# Interfaces_and_Connectors.net
KiCad netlist of a schematic drawn in Altium Designer
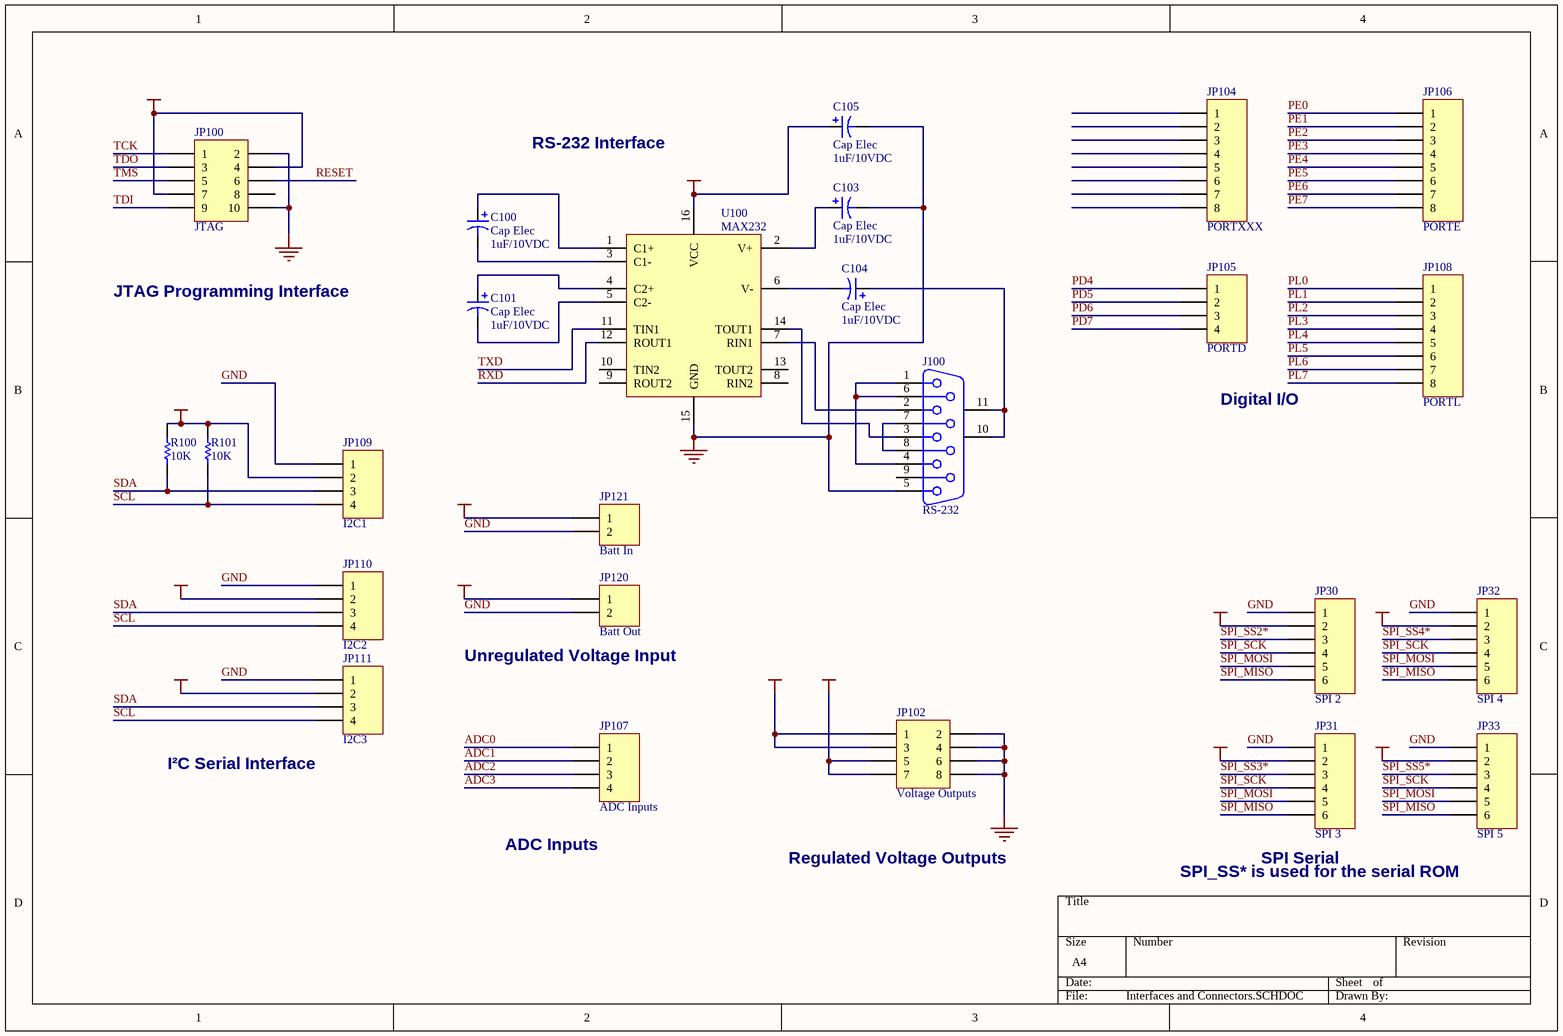
[diagram p0: Interfaces and Connectors.SCHDOC]

(export (version "E")
  (design (tool "Eeschema 10.0.6"))
  (components
    (comp (ref "C100")
      (value "Cap Elec")
      (footprint "CAPR5-4X5")
      (description "Polarized Capacitor (Axial)")
      (fields (field (name "ALTIUM_VALUE") "1uF/10VDC") (field (name "PUBLISHER") "Altium Limited"))
      (libsource (lib "Miscellaneous Devices") (part "Cap Pol2"))
    )
    (comp (ref "C101")
      (value "Cap Elec")
      (footprint "CAPR5-4X5")
      (description "Polarized Capacitor (Axial)")
      (fields (field (name "ALTIUM_VALUE") "1uF/10VDC") (field (name "PUBLISHER") "Altium Limited"))
      (libsource (lib "Miscellaneous Devices") (part "Cap Pol2"))
    )
    (comp (ref "C103")
      (value "Cap Elec")
      (footprint "CAPR5-4X5")
      (description "Polarized Capacitor (Axial)")
      (fields (field (name "ALTIUM_VALUE") "1uF/10VDC") (field (name "PUBLISHER") "Altium Limited"))
      (libsource (lib "Miscellaneous Devices") (part "Cap Pol2"))
    )
    (comp (ref "C104")
      (value "Cap Elec")
      (footprint "CAPR5-4X5")
      (description "Polarized Capacitor (Axial)")
      (fields (field (name "ALTIUM_VALUE") "1uF/10VDC") (field (name "PUBLISHER") "Altium Limited"))
      (libsource (lib "Miscellaneous Devices") (part "Cap Pol2"))
    )
    (comp (ref "C105")
      (value "Cap Elec")
      (footprint "CAPR5-4X5")
      (description "Polarized Capacitor (Axial)")
      (fields (field (name "ALTIUM_VALUE") "1uF/10VDC") (field (name "PUBLISHER") "Altium Limited"))
      (libsource (lib "Miscellaneous Devices") (part "Cap Pol2"))
    )
    (comp (ref "J100")
      (value "RS-232")
      (footprint "DSUB1.385-2H9")
      (description "Receptacle Assembly, 9 Position, Right Angle")
      (fields (field (name "PUBLISHER") "Altium Limited"))
      (libsource (lib "Miscellaneous Connectors") (part "D Connector 9"))
    )
    (comp (ref "JP30")
      (value "SPI 2")
      (footprint "HDR1X6")
      (description "Header, 6-Pin")
      (fields (field (name "PUBLISHER") "Altium Limited"))
      (libsource (lib "Miscellaneous Connectors") (part "Header 6"))
    )
    (comp (ref "JP31")
      (value "SPI 3")
      (footprint "HDR1X6")
      (description "Header, 6-Pin")
      (fields (field (name "PUBLISHER") "Altium Limited"))
      (libsource (lib "Miscellaneous Connectors") (part "Header 6"))
    )
    (comp (ref "JP32")
      (value "SPI 4")
      (footprint "HDR1X6")
      (description "Header, 6-Pin")
      (fields (field (name "PUBLISHER") "Altium Limited"))
      (libsource (lib "Miscellaneous Connectors") (part "Header 6"))
    )
    (comp (ref "JP33")
      (value "SPI 5")
      (footprint "HDR1X6")
      (description "Header, 6-Pin")
      (fields (field (name "PUBLISHER") "Altium Limited"))
      (libsource (lib "Miscellaneous Connectors") (part "Header 6"))
    )
    (comp (ref "JP100")
      (value "JTAG")
      (footprint "HDR2X5")
      (description "Header, 5-Pin, Dual row")
      (fields (field (name "PUBLISHER") "Altium Limited"))
      (libsource (lib "Miscellaneous Connectors") (part "Header 5X2"))
    )
    (comp (ref "JP102")
      (value "Voltage Outputs")
      (footprint "HDR2X4")
      (description "Header, 4-Pin, Dual row")
      (fields (field (name "PUBLISHER") "Altium Limited"))
      (libsource (lib "Miscellaneous Connectors") (part "Header 4X2"))
    )
    (comp (ref "JP104")
      (value "PORTXXX")
      (footprint "HDR1X8")
      (description "Header, 8-Pin")
      (fields (field (name "PUBLISHER") "Altium Limited"))
      (libsource (lib "Miscellaneous Connectors") (part "Header 8"))
    )
    (comp (ref "JP105")
      (value "PORTD")
      (footprint "HDR1X4")
      (description "Header, 4-Pin")
      (fields (field (name "PUBLISHER") "Altium Limited"))
      (libsource (lib "Miscellaneous Connectors") (part "Header 4"))
    )
    (comp (ref "JP106")
      (value "PORTE")
      (footprint "HDR1X8")
      (description "Header, 8-Pin")
      (fields (field (name "PUBLISHER") "Altium Limited"))
      (libsource (lib "Miscellaneous Connectors") (part "Header 8"))
    )
    (comp (ref "JP107")
      (value "ADC Inputs")
      (footprint "HDR1X4")
      (description "Header, 4-Pin")
      (fields (field (name "PUBLISHER") "Altium Limited"))
      (libsource (lib "Miscellaneous Connectors") (part "Header 4"))
    )
    (comp (ref "JP108")
      (value "PORTL")
      (footprint "HDR1X8")
      (description "Header, 8-Pin")
      (fields (field (name "PUBLISHER") "Altium Limited"))
      (libsource (lib "Miscellaneous Connectors") (part "Header 8"))
    )
    (comp (ref "JP109")
      (value "I2C1")
      (footprint "HDR1X4")
      (description "Header, 4-Pin")
      (fields (field (name "PUBLISHER") "Altium Limited"))
      (libsource (lib "Miscellaneous Connectors") (part "Header 4"))
    )
    (comp (ref "JP110")
      (value "I2C2")
      (footprint "HDR1X4")
      (description "Header, 4-Pin")
      (fields (field (name "PUBLISHER") "Altium Limited"))
      (libsource (lib "Miscellaneous Connectors") (part "Header 4"))
    )
    (comp (ref "JP111")
      (value "I2C3")
      (footprint "HDR1X4")
      (description "Header, 4-Pin")
      (fields (field (name "PUBLISHER") "Altium Limited"))
      (libsource (lib "Miscellaneous Connectors") (part "Header 4"))
    )
    (comp (ref "JP120")
      (value "Batt Out")
      (footprint "HDR1X2")
      (description "Header, 2-Pin")
      (fields (field (name "PUBLISHER") "Altium Limited"))
      (libsource (lib "Miscellaneous Connectors") (part "Header 2"))
    )
    (comp (ref "JP121")
      (value "Batt In")
      (footprint "HDR1X2")
      (description "Header, 2-Pin")
      (fields (field (name "PUBLISHER") "Altium Limited"))
      (libsource (lib "Miscellaneous Connectors") (part "Header 2"))
    )
    (comp (ref "R100")
      (value "10K")
      (footprint "AXIAL-0.3")
      (description "Resistor")
      (fields (field (name "PUBLISHER") "Altium Limited"))
      (libsource (lib "Miscellaneous Devices") (part "Res1"))
    )
    (comp (ref "R101")
      (value "10K")
      (footprint "AXIAL-0.3")
      (description "Resistor")
      (fields (field (name "PUBLISHER") "Altium Limited"))
      (libsource (lib "Miscellaneous Devices") (part "Res1"))
    )
    (comp (ref "U100")
      (value "MAX232")
      (footprint "SO-G16/C5.85")
      (description "Maxim RS-232 Transceiver")
      (libsource (lib "Schematic Library") (part "MAX232"))
    )
  )
  (nets
    (net (code "1") (name "/ADC0") (class "Default")
      (node (ref "JP107") (pin "1") (pinfunction "1_1") (pintype "passive"))
    )
    (net (code "2") (name "/ADC1") (class "Default")
      (node (ref "JP107") (pin "2") (pinfunction "2_2") (pintype "passive"))
    )
    (net (code "3") (name "/ADC2") (class "Default")
      (node (ref "JP107") (pin "3") (pinfunction "3_3") (pintype "passive"))
    )
    (net (code "4") (name "/ADC3") (class "Default")
      (node (ref "JP107") (pin "4") (pinfunction "4_4") (pintype "passive"))
    )
    (net (code "5") (name "/PD4") (class "Default")
      (node (ref "JP105") (pin "1") (pinfunction "1_1") (pintype "passive"))
    )
    (net (code "6") (name "/PD5") (class "Default")
      (node (ref "JP105") (pin "2") (pinfunction "2_2") (pintype "passive"))
    )
    (net (code "7") (name "/PD6") (class "Default")
      (node (ref "JP105") (pin "3") (pinfunction "3_3") (pintype "passive"))
    )
    (net (code "8") (name "/PD7") (class "Default")
      (node (ref "JP105") (pin "4") (pinfunction "4_4") (pintype "passive"))
    )
    (net (code "9") (name "/PE0") (class "Default")
      (node (ref "JP106") (pin "1") (pinfunction "1_1") (pintype "passive"))
    )
    (net (code "10") (name "/PE1") (class "Default")
      (node (ref "JP106") (pin "2") (pinfunction "2_2") (pintype "passive"))
    )
    (net (code "11") (name "/PE2") (class "Default")
      (node (ref "JP106") (pin "3") (pinfunction "3_3") (pintype "passive"))
    )
    (net (code "12") (name "/PE3") (class "Default")
      (node (ref "JP106") (pin "4") (pinfunction "4_4") (pintype "passive"))
    )
    (net (code "13") (name "/PE4") (class "Default")
      (node (ref "JP106") (pin "5") (pinfunction "5_5") (pintype "passive"))
    )
    (net (code "14") (name "/PE5") (class "Default")
      (node (ref "JP106") (pin "6") (pinfunction "6_6") (pintype "passive"))
    )
    (net (code "15") (name "/PE6") (class "Default")
      (node (ref "JP106") (pin "7") (pinfunction "7_7") (pintype "passive"))
    )
    (net (code "16") (name "/PE7") (class "Default")
      (node (ref "JP106") (pin "8") (pinfunction "8_8") (pintype "passive"))
    )
    (net (code "17") (name "/PL0") (class "Default")
      (node (ref "JP108") (pin "1") (pinfunction "1_1") (pintype "passive"))
    )
    (net (code "18") (name "/PL1") (class "Default")
      (node (ref "JP108") (pin "2") (pinfunction "2_2") (pintype "passive"))
    )
    (net (code "19") (name "/PL2") (class "Default")
      (node (ref "JP108") (pin "3") (pinfunction "3_3") (pintype "passive"))
    )
    (net (code "20") (name "/PL3") (class "Default")
      (node (ref "JP108") (pin "4") (pinfunction "4_4") (pintype "passive"))
    )
    (net (code "21") (name "/PL4") (class "Default")
      (node (ref "JP108") (pin "5") (pinfunction "5_5") (pintype "passive"))
    )
    (net (code "22") (name "/PL5") (class "Default")
      (node (ref "JP108") (pin "6") (pinfunction "6_6") (pintype "passive"))
    )
    (net (code "23") (name "/PL6") (class "Default")
      (node (ref "JP108") (pin "7") (pinfunction "7_7") (pintype "passive"))
    )
    (net (code "24") (name "/PL7") (class "Default")
      (node (ref "JP108") (pin "8") (pinfunction "8_8") (pintype "passive"))
    )
    (net (code "25") (name "/RESET") (class "Default")
      (node (ref "JP100") (pin "6") (pinfunction "6_6") (pintype "passive"))
    )
    (net (code "26") (name "/RXD") (class "Default")
      (node (ref "U100") (pin "12") (pinfunction "ROUT1_12") (pintype "passive"))
    )
    (net (code "27") (name "/SCL") (class "Default")
      (node (ref "JP109") (pin "4") (pinfunction "4_4") (pintype "passive"))
      (node (ref "JP110") (pin "4") (pinfunction "4_4") (pintype "passive"))
      (node (ref "JP111") (pin "4") (pinfunction "4_4") (pintype "passive"))
      (node (ref "R101") (pin "1") (pinfunction "1_1") (pintype "passive"))
    )
    (net (code "28") (name "/SDA") (class "Default")
      (node (ref "JP109") (pin "3") (pinfunction "3_3") (pintype "passive"))
      (node (ref "JP110") (pin "3") (pinfunction "3_3") (pintype "passive"))
      (node (ref "JP111") (pin "3") (pinfunction "3_3") (pintype "passive"))
      (node (ref "R100") (pin "1") (pinfunction "1_1") (pintype "passive"))
    )
    (net (code "29") (name "/SPI_MISO") (class "Default")
      (node (ref "JP30") (pin "6") (pinfunction "6_6") (pintype "passive"))
      (node (ref "JP31") (pin "6") (pinfunction "6_6") (pintype "passive"))
      (node (ref "JP32") (pin "6") (pinfunction "6_6") (pintype "passive"))
      (node (ref "JP33") (pin "6") (pinfunction "6_6") (pintype "passive"))
    )
    (net (code "30") (name "/SPI_MOSI") (class "Default")
      (node (ref "JP30") (pin "5") (pinfunction "5_5") (pintype "passive"))
      (node (ref "JP31") (pin "5") (pinfunction "5_5") (pintype "passive"))
      (node (ref "JP32") (pin "5") (pinfunction "5_5") (pintype "passive"))
      (node (ref "JP33") (pin "5") (pinfunction "5_5") (pintype "passive"))
    )
    (net (code "31") (name "/SPI_SCK") (class "Default")
      (node (ref "JP30") (pin "4") (pinfunction "4_4") (pintype "passive"))
      (node (ref "JP31") (pin "4") (pinfunction "4_4") (pintype "passive"))
      (node (ref "JP32") (pin "4") (pinfunction "4_4") (pintype "passive"))
      (node (ref "JP33") (pin "4") (pinfunction "4_4") (pintype "passive"))
    )
    (net (code "32") (name "/SPI_SS2*") (class "Default")
      (node (ref "JP30") (pin "3") (pinfunction "3_3") (pintype "passive"))
    )
    (net (code "33") (name "/SPI_SS3*") (class "Default")
      (node (ref "JP31") (pin "3") (pinfunction "3_3") (pintype "passive"))
    )
    (net (code "34") (name "/SPI_SS4*") (class "Default")
      (node (ref "JP32") (pin "3") (pinfunction "3_3") (pintype "passive"))
    )
    (net (code "35") (name "/SPI_SS5*") (class "Default")
      (node (ref "JP33") (pin "3") (pinfunction "3_3") (pintype "passive"))
    )
    (net (code "36") (name "/TCK") (class "Default")
      (node (ref "JP100") (pin "1") (pinfunction "1_1") (pintype "passive"))
    )
    (net (code "37") (name "/TDI") (class "Default")
      (node (ref "JP100") (pin "9") (pinfunction "9_9") (pintype "passive"))
    )
    (net (code "38") (name "/TDO") (class "Default")
      (node (ref "JP100") (pin "3") (pinfunction "3_3") (pintype "passive"))
    )
    (net (code "39") (name "/TMS") (class "Default")
      (node (ref "JP100") (pin "5") (pinfunction "5_5") (pintype "passive"))
    )
    (net (code "40") (name "/TXD") (class "Default")
      (node (ref "U100") (pin "11") (pinfunction "TIN1_11") (pintype "passive"))
    )
    (net (code "41") (name "5V") (class "Default")
      (node (ref "C105") (pin "1") (pinfunction "1_1") (pintype "passive"))
      (node (ref "JP100") (pin "4") (pinfunction "4_4") (pintype "passive"))
      (node (ref "JP100") (pin "7") (pinfunction "7_7") (pintype "passive"))
      (node (ref "JP102") (pin "5") (pinfunction "5_5") (pintype "passive"))
      (node (ref "JP102") (pin "7") (pinfunction "7_7") (pintype "passive"))
      (node (ref "JP109") (pin "2") (pinfunction "2_2") (pintype "passive"))
      (node (ref "JP110") (pin "2") (pinfunction "2_2") (pintype "passive"))
      (node (ref "JP111") (pin "2") (pinfunction "2_2") (pintype "passive"))
      (node (ref "JP30") (pin "2") (pinfunction "2_2") (pintype "passive"))
      (node (ref "JP31") (pin "2") (pinfunction "2_2") (pintype "passive"))
      (node (ref "JP32") (pin "2") (pinfunction "2_2") (pintype "passive"))
      (node (ref "JP33") (pin "2") (pinfunction "2_2") (pintype "passive"))
      (node (ref "R100") (pin "2") (pinfunction "2_2") (pintype "passive"))
      (node (ref "R101") (pin "2") (pinfunction "2_2") (pintype "passive"))
      (node (ref "U100") (pin "16") (pinfunction "VCC_16") (pintype "passive"))
    )
    (net (code "42") (name "9V") (class "Default")
      (node (ref "JP102") (pin "1") (pinfunction "1_1") (pintype "passive"))
      (node (ref "JP102") (pin "3") (pinfunction "3_3") (pintype "passive"))
    )
    (net (code "43") (name "GND") (class "Default")
      (node (ref "C103") (pin "2") (pinfunction "2_2") (pintype "passive"))
      (node (ref "C105") (pin "2") (pinfunction "2_2") (pintype "passive"))
      (node (ref "J100") (pin "5") (pinfunction "5_5") (pintype "passive"))
      (node (ref "JP100") (pin "10") (pinfunction "10_10") (pintype "passive"))
      (node (ref "JP100") (pin "2") (pinfunction "2_2") (pintype "passive"))
      (node (ref "JP102") (pin "2") (pinfunction "2_2") (pintype "passive"))
      (node (ref "JP102") (pin "4") (pinfunction "4_4") (pintype "passive"))
      (node (ref "JP102") (pin "6") (pinfunction "6_6") (pintype "passive"))
      (node (ref "JP102") (pin "8") (pinfunction "8_8") (pintype "passive"))
      (node (ref "JP109") (pin "1") (pinfunction "1_1") (pintype "passive"))
      (node (ref "JP110") (pin "1") (pinfunction "1_1") (pintype "passive"))
      (node (ref "JP111") (pin "1") (pinfunction "1_1") (pintype "passive"))
      (node (ref "JP120") (pin "2") (pinfunction "2_2") (pintype "passive"))
      (node (ref "JP121") (pin "2") (pinfunction "2_2") (pintype "passive"))
      (node (ref "JP30") (pin "1") (pinfunction "1_1") (pintype "passive"))
      (node (ref "JP31") (pin "1") (pinfunction "1_1") (pintype "passive"))
      (node (ref "JP32") (pin "1") (pinfunction "1_1") (pintype "passive"))
      (node (ref "JP33") (pin "1") (pinfunction "1_1") (pintype "passive"))
      (node (ref "U100") (pin "15") (pinfunction "GND_15") (pintype "passive"))
    )
    (net (code "44") (name "Net-(J100-MH1)") (class "Default")
      (node (ref "C104") (pin "1") (pinfunction "1_1") (pintype "passive"))
      (node (ref "J100") (pin "10") (pinfunction "MH1_10") (pintype "passive"))
      (node (ref "J100") (pin "11") (pinfunction "MH2_11") (pintype "passive"))
    )
    (net (code "45") (name "Net-(J100-Pad1)") (class "Default")
      (node (ref "J100") (pin "1") (pinfunction "1_1") (pintype "passive"))
      (node (ref "J100") (pin "4") (pinfunction "4_4") (pintype "passive"))
      (node (ref "J100") (pin "6") (pinfunction "6_6") (pintype "passive"))
    )
    (net (code "46") (name "Net-(J100-Pad7)") (class "Default")
      (node (ref "J100") (pin "7") (pinfunction "7_7") (pintype "passive"))
      (node (ref "J100") (pin "8") (pinfunction "8_8") (pintype "passive"))
    )
    (net (code "47") (name "Net-(U100-C1+)") (class "Default")
      (node (ref "C100") (pin "1") (pinfunction "1_1") (pintype "passive"))
      (node (ref "U100") (pin "1") (pinfunction "C1+_1") (pintype "passive"))
    )
    (net (code "48") (name "Net-(U100-C1-)") (class "Default")
      (node (ref "C100") (pin "2") (pinfunction "2_2") (pintype "passive"))
      (node (ref "U100") (pin "3") (pinfunction "C1-_3") (pintype "passive"))
    )
    (net (code "49") (name "Net-(U100-C2+)") (class "Default")
      (node (ref "C101") (pin "1") (pinfunction "1_1") (pintype "passive"))
      (node (ref "U100") (pin "4") (pinfunction "C2+_4") (pintype "passive"))
    )
    (net (code "50") (name "Net-(U100-C2-)") (class "Default")
      (node (ref "C101") (pin "2") (pinfunction "2_2") (pintype "passive"))
      (node (ref "U100") (pin "5") (pinfunction "C2-_5") (pintype "passive"))
    )
    (net (code "51") (name "Net-(U100-RIN1)") (class "Default")
      (node (ref "J100") (pin "2") (pinfunction "2_2") (pintype "passive"))
      (node (ref "U100") (pin "7") (pinfunction "RIN1_7") (pintype "passive"))
    )
    (net (code "52") (name "Net-(U100-TOUT1)") (class "Default")
      (node (ref "J100") (pin "3") (pinfunction "3_3") (pintype "passive"))
      (node (ref "U100") (pin "14") (pinfunction "TOUT1_14") (pintype "passive"))
    )
    (net (code "53") (name "Net-(U100-V+)") (class "Default")
      (node (ref "C103") (pin "1") (pinfunction "1_1") (pintype "passive"))
      (node (ref "U100") (pin "2") (pinfunction "V+_2") (pintype "passive"))
    )
    (net (code "54") (name "Net-(U100-V-)") (class "Default")
      (node (ref "C104") (pin "2") (pinfunction "2_2") (pintype "passive"))
      (node (ref "U100") (pin "6") (pinfunction "V-_6") (pintype "passive"))
    )
    (net (code "55") (name "VBat") (class "Default")
      (node (ref "JP120") (pin "1") (pinfunction "1_1") (pintype "passive"))
      (node (ref "JP121") (pin "1") (pinfunction "1_1") (pintype "passive"))
    )
    (net (code "56") (name "unconnected-(J100-Pad9)") (class "Default")
      (node (ref "J100") (pin "9") (pinfunction "9_9") (pintype "passive"))
    )
    (net (code "57") (name "unconnected-(JP100-Pad8)") (class "Default")
      (node (ref "JP100") (pin "8") (pinfunction "8_8") (pintype "passive"))
    )
    (net (code "58") (name "unconnected-(JP104-Pad1)") (class "Default")
      (node (ref "JP104") (pin "1") (pinfunction "1_1") (pintype "passive"))
    )
    (net (code "59") (name "unconnected-(JP104-Pad2)") (class "Default")
      (node (ref "JP104") (pin "2") (pinfunction "2_2") (pintype "passive"))
    )
    (net (code "60") (name "unconnected-(JP104-Pad3)") (class "Default")
      (node (ref "JP104") (pin "3") (pinfunction "3_3") (pintype "passive"))
    )
    (net (code "61") (name "unconnected-(JP104-Pad4)") (class "Default")
      (node (ref "JP104") (pin "4") (pinfunction "4_4") (pintype "passive"))
    )
    (net (code "62") (name "unconnected-(JP104-Pad5)") (class "Default")
      (node (ref "JP104") (pin "5") (pinfunction "5_5") (pintype "passive"))
    )
    (net (code "63") (name "unconnected-(JP104-Pad6)") (class "Default")
      (node (ref "JP104") (pin "6") (pinfunction "6_6") (pintype "passive"))
    )
    (net (code "64") (name "unconnected-(JP104-Pad7)") (class "Default")
      (node (ref "JP104") (pin "7") (pinfunction "7_7") (pintype "passive"))
    )
    (net (code "65") (name "unconnected-(JP104-Pad8)") (class "Default")
      (node (ref "JP104") (pin "8") (pinfunction "8_8") (pintype "passive"))
    )
    (net (code "66") (name "unconnected-(U100-RIN2-Pad8)") (class "Default")
      (node (ref "U100") (pin "8") (pinfunction "RIN2_8") (pintype "passive"))
    )
    (net (code "67") (name "unconnected-(U100-ROUT2-Pad9)") (class "Default")
      (node (ref "U100") (pin "9") (pinfunction "ROUT2_9") (pintype "passive"))
    )
    (net (code "68") (name "unconnected-(U100-TIN2-Pad10)") (class "Default")
      (node (ref "U100") (pin "10") (pinfunction "TIN2_10") (pintype "passive"))
    )
    (net (code "69") (name "unconnected-(U100-TOUT2-Pad13)") (class "Default")
      (node (ref "U100") (pin "13") (pinfunction "TOUT2_13") (pintype "passive"))
    )
  )
)
